# Adafruit_HDC1008.net
KiCad netlist of a schematic drawn in EAGLE
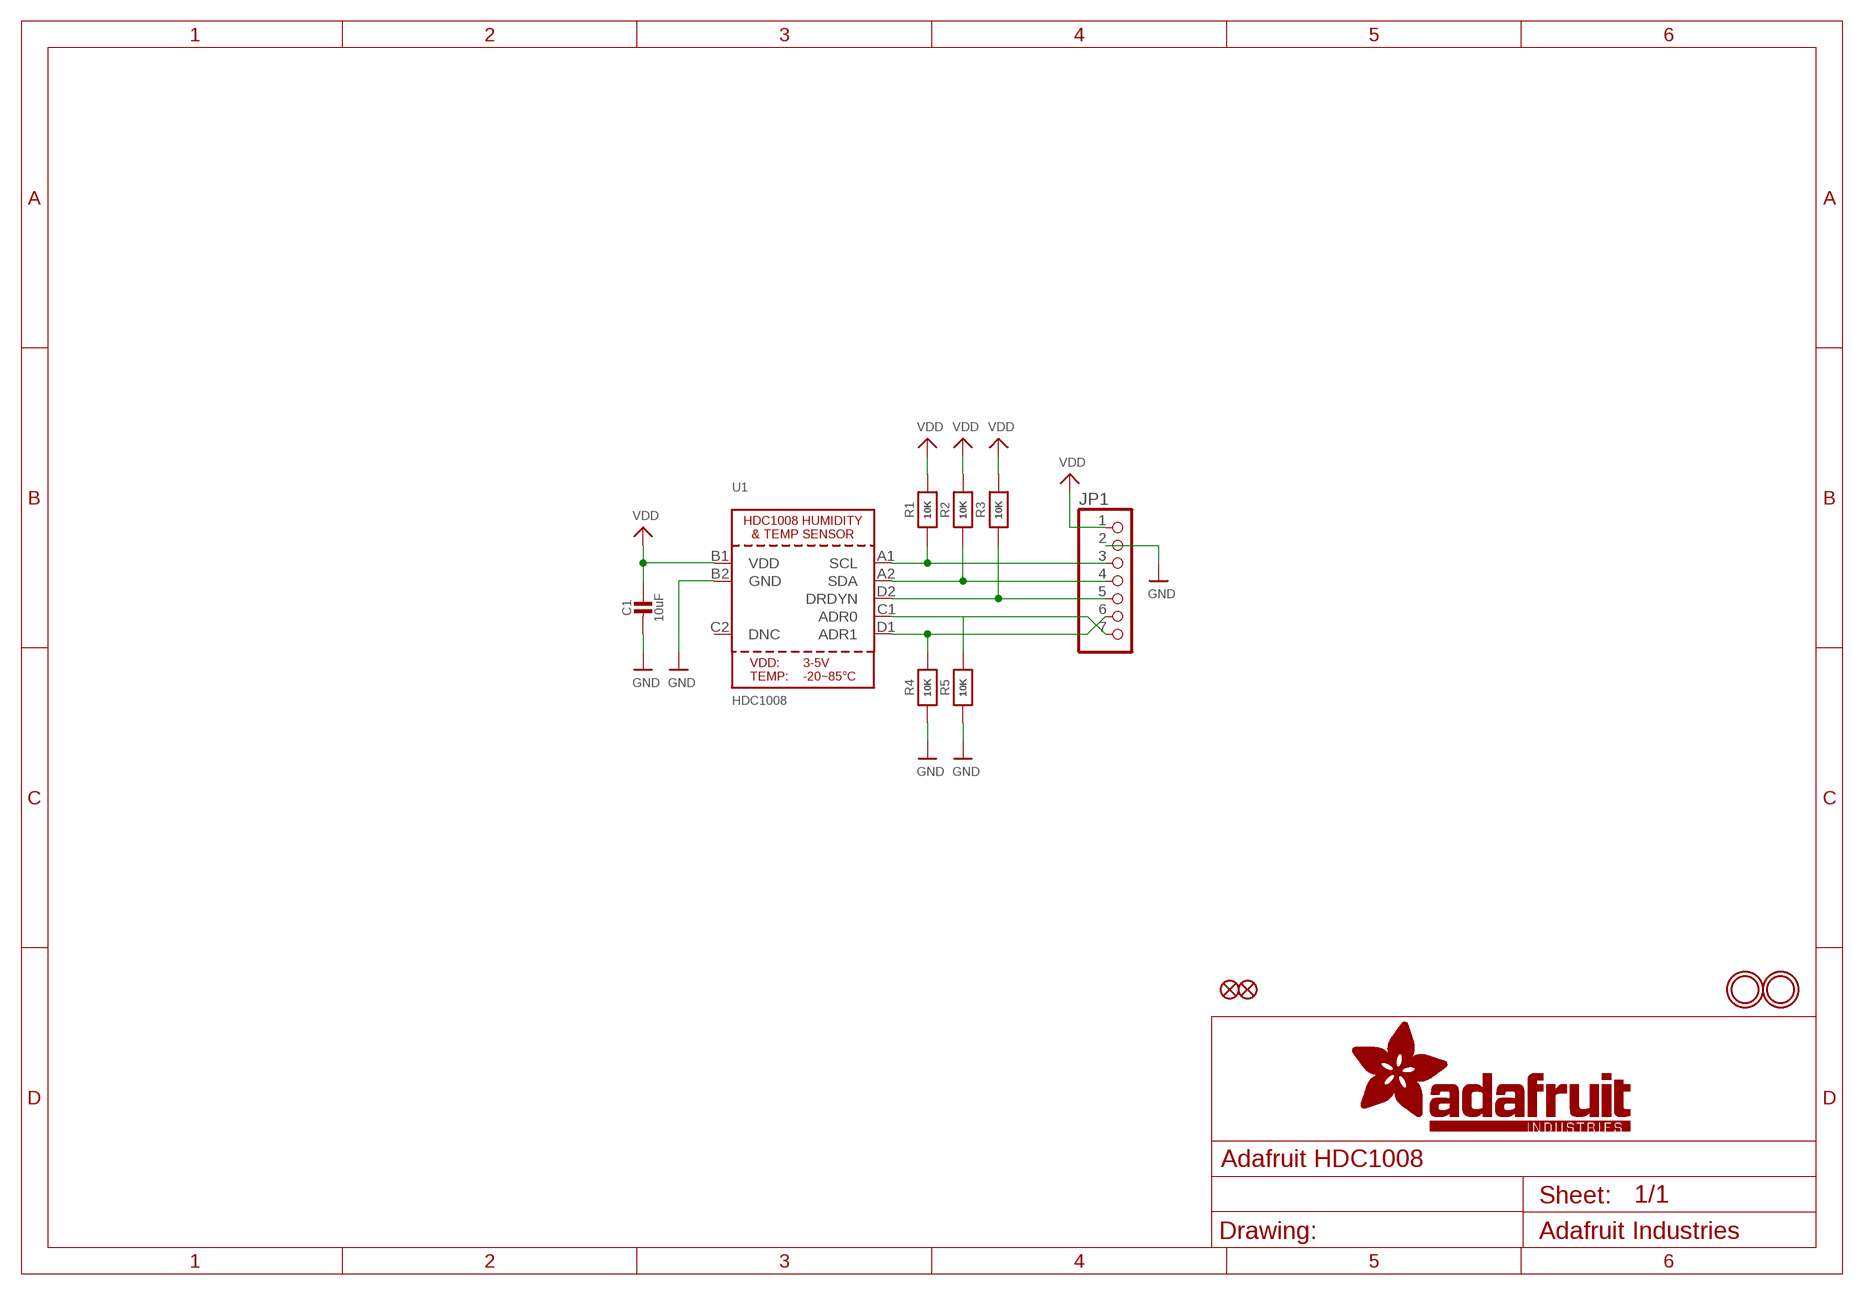
[diagram p0: schematic, sheet 1]

(export (version "E")
  (design (tool "Eeschema 10.0.6"))
  (components
    (comp (ref "C1")
      (value "10uF")
      (footprint "eagle-import:0805-NO")
      (libsource (lib "eagle-import") (part "CAP_CERAMIC0805-NOOUTLINE"))
    )
    (comp (ref "FID1")
      (value "FIDUCIAL\"\"")
      (footprint "eagle-import:FIDUCIAL_1MM")
      (libsource (lib "eagle-import") (part "FIDUCIAL{dblquote}{dblquote}"))
    )
    (comp (ref "FID2")
      (value "FIDUCIAL\"\"")
      (footprint "eagle-import:FIDUCIAL_1MM")
      (libsource (lib "eagle-import") (part "FIDUCIAL{dblquote}{dblquote}"))
    )
    (comp (ref "JP1")
      (value "HEADER-1X770MIL")
      (footprint "eagle-import:1X07_ROUND_70")
      (libsource (lib "eagle-import") (part "HEADER-1X770MIL"))
    )
    (comp (ref "R1")
      (value "10K")
      (footprint "eagle-import:0805-NO")
      (libsource (lib "eagle-import") (part "RESISTOR0805_NOOUTLINE"))
    )
    (comp (ref "R2")
      (value "10K")
      (footprint "eagle-import:_0805MP")
      (libsource (lib "eagle-import") (part "RESISTOR_0805MP"))
    )
    (comp (ref "R3")
      (value "10K")
      (footprint "eagle-import:0805-NO")
      (libsource (lib "eagle-import") (part "RESISTOR0805_NOOUTLINE"))
    )
    (comp (ref "R4")
      (value "10K")
      (footprint "eagle-import:0805-NO")
      (libsource (lib "eagle-import") (part "RESISTOR0805_NOOUTLINE"))
    )
    (comp (ref "R5")
      (value "10K")
      (footprint "eagle-import:0805-NO")
      (libsource (lib "eagle-import") (part "RESISTOR0805_NOOUTLINE"))
    )
    (comp (ref "U$2")
      (value "MOUNTINGHOLE2.5")
      (footprint "eagle-import:MOUNTINGHOLE_2.5_PLATED")
      (libsource (lib "eagle-import") (part "MOUNTINGHOLE2.5"))
    )
    (comp (ref "U$3")
      (value "MOUNTINGHOLE2.5")
      (footprint "eagle-import:MOUNTINGHOLE_2.5_PLATED")
      (libsource (lib "eagle-import") (part "MOUNTINGHOLE2.5"))
    )
    (comp (ref "U1")
      (value "HDC1008")
      (footprint "eagle-import:DSBGA8_HDC1008")
      (libsource (lib "eagle-import") (part "HDC1008"))
    )
  )
  (nets
    (net (code "1") (name "GND") (class "Default")
      (node (ref "C1") (pin "2") (pinfunction "2_2") (pintype "passive"))
      (node (ref "JP1") (pin "2") (pinfunction "2_2") (pintype "passive"))
      (node (ref "R4") (pin "1") (pinfunction "1_1") (pintype "passive"))
      (node (ref "R5") (pin "1") (pinfunction "1_1") (pintype "passive"))
      (node (ref "U1") (pin "B2") (pinfunction "GND_B2") (pintype "power_in"))
    )
    (net (code "2") (name "Net-(U1-ADR0)") (class "Default")
      (node (ref "JP1") (pin "7") (pinfunction "7_7") (pintype "passive"))
      (node (ref "R5") (pin "2") (pinfunction "2_2") (pintype "passive"))
      (node (ref "U1") (pin "C1") (pinfunction "ADR0_C1") (pintype "input"))
    )
    (net (code "3") (name "Net-(U1-ADR1)") (class "Default")
      (node (ref "JP1") (pin "6") (pinfunction "6_6") (pintype "passive"))
      (node (ref "R4") (pin "2") (pinfunction "2_2") (pintype "passive"))
      (node (ref "U1") (pin "D1") (pinfunction "ADR1_D1") (pintype "input"))
    )
    (net (code "4") (name "Net-(U1-DRDYN)") (class "Default")
      (node (ref "JP1") (pin "5") (pinfunction "5_5") (pintype "passive"))
      (node (ref "R3") (pin "1") (pinfunction "1_1") (pintype "passive"))
      (node (ref "U1") (pin "D2") (pinfunction "DRDYN_D2") (pintype "output"))
    )
    (net (code "5") (name "Net-(U1-SCL)") (class "Default")
      (node (ref "JP1") (pin "3") (pinfunction "3_3") (pintype "passive"))
      (node (ref "R1") (pin "1") (pinfunction "1_1") (pintype "passive"))
      (node (ref "U1") (pin "A1") (pinfunction "SCL_A1") (pintype "bidirectional"))
    )
    (net (code "6") (name "Net-(U1-SDA)") (class "Default")
      (node (ref "JP1") (pin "4") (pinfunction "4_4") (pintype "passive"))
      (node (ref "R2") (pin "1") (pinfunction "1_1") (pintype "passive"))
      (node (ref "U1") (pin "A2") (pinfunction "SDA_A2") (pintype "bidirectional"))
    )
    (net (code "7") (name "VDD") (class "Default")
      (node (ref "C1") (pin "1") (pinfunction "1_1") (pintype "passive"))
      (node (ref "JP1") (pin "1") (pinfunction "1_1") (pintype "passive"))
      (node (ref "R1") (pin "2") (pinfunction "2_2") (pintype "passive"))
      (node (ref "R2") (pin "2") (pinfunction "2_2") (pintype "passive"))
      (node (ref "R3") (pin "2") (pinfunction "2_2") (pintype "passive"))
      (node (ref "U1") (pin "B1") (pinfunction "VDD_B1") (pintype "power_in"))
    )
    (net (code "8") (name "unconnected-(U1-DNC-PadC2)") (class "Default")
      (node (ref "U1") (pin "C2") (pinfunction "DNC_C2") (pintype "no_connect"))
    )
  )
)
